# enc28j60.net
KiCad netlist of a schematic drawn in Altium Designer
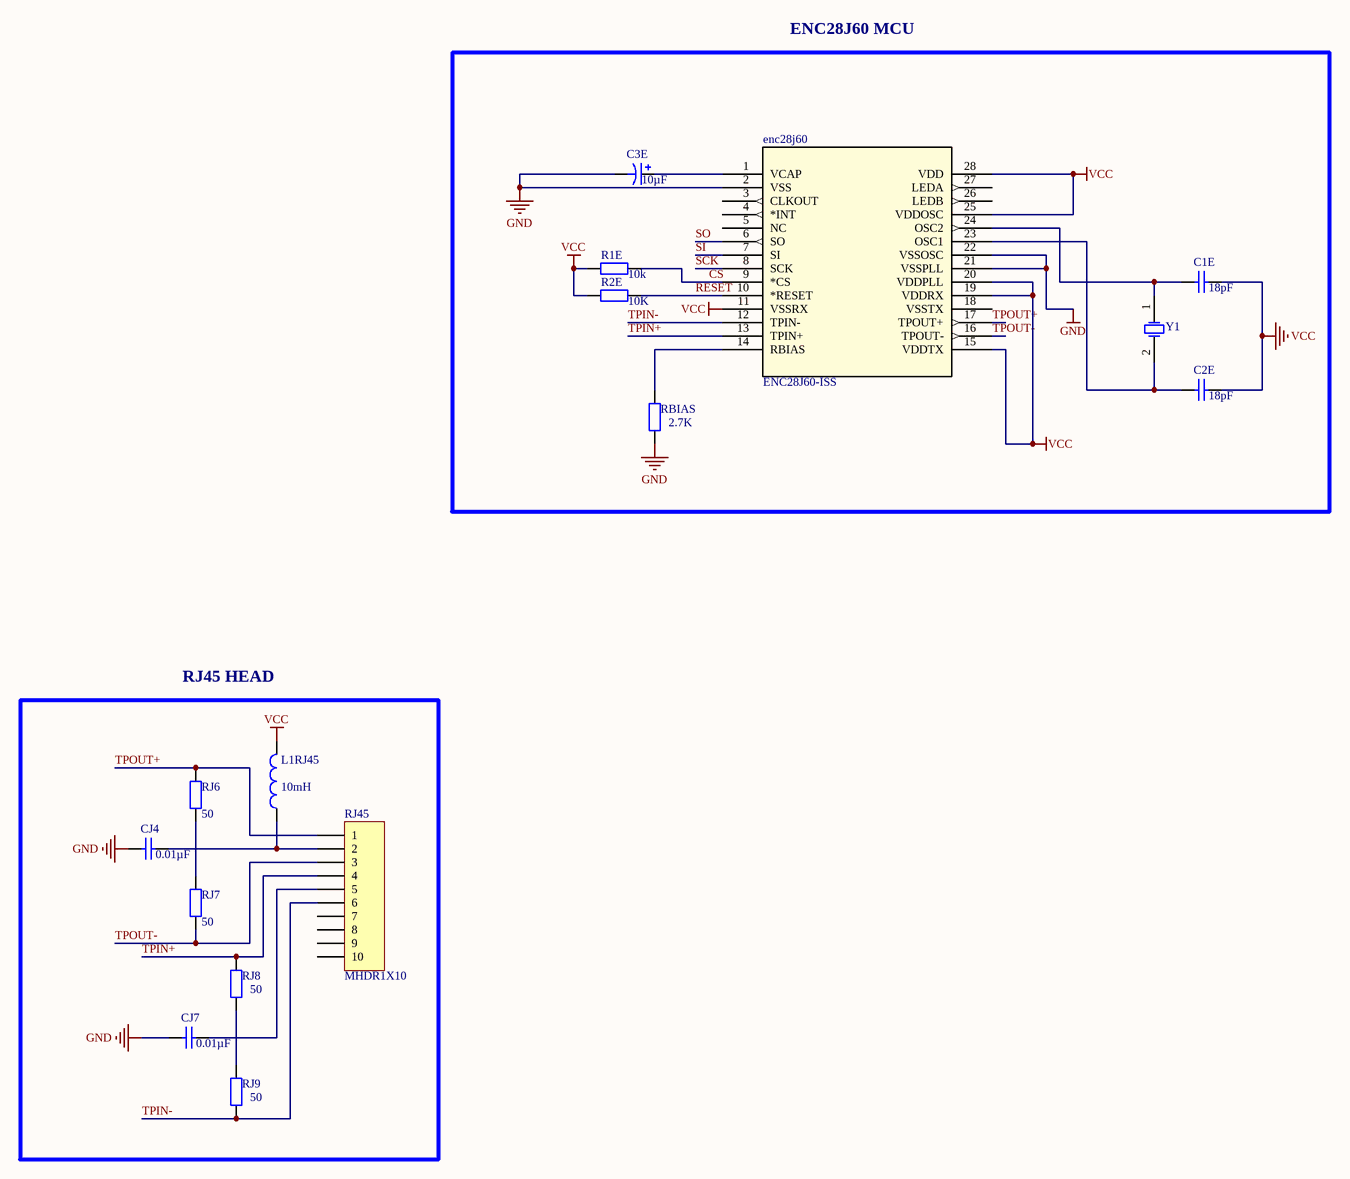
[diagram p0: enc28j60.SchDoc]

(export (version "E")
  (design (tool "Eeschema 10.0.6"))
  (components
    (comp (ref "C1E")
      (value "18pF")
      (footprint "RAD-0.3")
      (description "Capacitor")
      (fields (field (name "Comment") "Cap") (field (name "PUBLISHER") "Altium Limited"))
      (libsource (lib "Miscellaneous Devices") (part "Cap"))
    )
    (comp (ref "C2E")
      (value "18pF")
      (footprint "RAD-0.3")
      (description "Capacitor")
      (fields (field (name "Comment") "Cap") (field (name "PUBLISHER") "Altium Limited"))
      (libsource (lib "Miscellaneous Devices") (part "Cap"))
    )
    (comp (ref "C3E")
      (value "10µF")
      (footprint "RB7.6-15")
      (description "Polarized Capacitor (Radial)")
      (fields (field (name "PUBLISHER") "Altium Limited"))
      (libsource (lib "Miscellaneous Devices") (part "Cap Pol1"))
    )
    (comp (ref "CJ4")
      (value "0.01µF")
      (footprint "RAD-0.3")
      (description "Capacitor")
      (fields (field (name "Comment") "Cap") (field (name "PUBLISHER") "Altium Limited"))
      (libsource (lib "Miscellaneous Devices") (part "Cap"))
    )
    (comp (ref "CJ7")
      (value "0.01µF")
      (footprint "RAD-0.3")
      (description "Capacitor")
      (fields (field (name "Comment") "Cap") (field (name "PUBLISHER") "Altium Limited"))
      (libsource (lib "Miscellaneous Devices") (part "Cap"))
    )
    (comp (ref "enc28j60")
      (value "ENC28J60-ISS")
      (footprint "SSOP28_MC_MCH")
      (description "No Description Available")
      (libsource (lib "ENC28J60-ISS") (part "ENC28J60-ISS"))
    )
    (comp (ref "L1RJ45")
      (value "10mH")
      (footprint "0402-A")
      (description "Inductor")
      (fields (field (name "PUBLISHER") "Altium Limited"))
      (libsource (lib "Miscellaneous Devices") (part "Inductor"))
    )
    (comp (ref "R1E")
      (value "10k")
      (footprint "AXIAL-0.4")
      (description "Resistor")
      (fields (field (name "PUBLISHER") "Altium Limited"))
      (libsource (lib "Miscellaneous Devices") (part "Res2"))
    )
    (comp (ref "R2E")
      (value "10K")
      (footprint "AXIAL-0.4")
      (description "Resistor")
      (fields (field (name "PUBLISHER") "Altium Limited"))
      (libsource (lib "Miscellaneous Devices") (part "Res2"))
    )
    (comp (ref "RBIAS")
      (value "2.7K")
      (footprint "AXIAL-0.4")
      (description "Resistor")
      (fields (field (name "PUBLISHER") "Altium Limited"))
      (libsource (lib "") (part "Res2_1"))
    )
    (comp (ref "RJ6")
      (value "50")
      (footprint "AXIAL-0.4")
      (description "Resistor")
      (fields (field (name "PUBLISHER") "Altium Limited"))
      (libsource (lib "") (part "Res2_1"))
    )
    (comp (ref "RJ7")
      (value "50")
      (footprint "AXIAL-0.4")
      (description "Resistor")
      (fields (field (name "PUBLISHER") "Altium Limited"))
      (libsource (lib "") (part "Res2_1"))
    )
    (comp (ref "RJ8")
      (value "50")
      (footprint "AXIAL-0.4")
      (description "Resistor")
      (fields (field (name "PUBLISHER") "Altium Limited"))
      (libsource (lib "") (part "Res2_1"))
    )
    (comp (ref "RJ9")
      (value "50")
      (footprint "AXIAL-0.4")
      (description "Resistor")
      (fields (field (name "PUBLISHER") "Altium Limited"))
      (libsource (lib "") (part "Res2_1"))
    )
    (comp (ref "RJ45")
      (value "MHDR1X10")
      (footprint "MHDR1X10")
      (description "Header, 10-Pin")
      (fields (field (name "PUBLISHER") "Altium Limited"))
      (libsource (lib "Miscellaneous Connectors") (part "MHDR1X10"))
    )
    (comp (ref "Y1")
      (value "XTAL")
      (footprint "R38")
      (description "Crystal Oscillator")
      (fields (field (name "PUBLISHER") "Altium Limited"))
      (libsource (lib "Miscellaneous Devices") (part "XTAL"))
    )
  )
  (nets
    (net (code "1") (name "/CS") (class "Default")
      (node (ref "R1E") (pin "2") (pinfunction "2_2") (pintype "passive"))
      (node (ref "enc28j60") (pin "9") (pinfunction "*CS_9") (pintype "passive"))
    )
    (net (code "2") (name "/RESET") (class "Default")
      (node (ref "R2E") (pin "2") (pinfunction "2_2") (pintype "passive"))
      (node (ref "enc28j60") (pin "10") (pinfunction "*RESET_10") (pintype "passive"))
    )
    (net (code "3") (name "/SCK") (class "Default")
      (node (ref "enc28j60") (pin "8") (pinfunction "SCK_8") (pintype "passive"))
    )
    (net (code "4") (name "/SI") (class "Default")
      (node (ref "enc28j60") (pin "7") (pinfunction "SI_7") (pintype "passive"))
    )
    (net (code "5") (name "/SO") (class "Default")
      (node (ref "enc28j60") (pin "6") (pinfunction "SO_6") (pintype "output"))
    )
    (net (code "6") (name "/TPIN+") (class "Default")
      (node (ref "RJ45") (pin "4") (pinfunction "4_4") (pintype "passive"))
      (node (ref "RJ8") (pin "2") (pinfunction "2_2") (pintype "passive"))
      (node (ref "enc28j60") (pin "13") (pinfunction "TPIN+_13") (pintype "passive"))
    )
    (net (code "7") (name "/TPIN-") (class "Default")
      (node (ref "RJ45") (pin "6") (pinfunction "6_6") (pintype "passive"))
      (node (ref "RJ9") (pin "1") (pinfunction "1_1") (pintype "passive"))
      (node (ref "enc28j60") (pin "12") (pinfunction "TPIN-_12") (pintype "passive"))
    )
    (net (code "8") (name "/TPOUT+") (class "Default")
      (node (ref "RJ45") (pin "1") (pinfunction "1_1") (pintype "passive"))
      (node (ref "RJ6") (pin "2") (pinfunction "2_2") (pintype "passive"))
      (node (ref "enc28j60") (pin "17") (pinfunction "TPOUT+_17") (pintype "output"))
    )
    (net (code "9") (name "/TPOUT-") (class "Default")
      (node (ref "RJ45") (pin "3") (pinfunction "3_3") (pintype "passive"))
      (node (ref "RJ7") (pin "1") (pinfunction "1_1") (pintype "passive"))
      (node (ref "enc28j60") (pin "16") (pinfunction "TPOUT-_16") (pintype "output"))
    )
    (net (code "10") (name "GND") (class "Default")
      (node (ref "C3E") (pin "2") (pinfunction "2_2") (pintype "passive"))
      (node (ref "CJ4") (pin "1") (pinfunction "1_1") (pintype "passive"))
      (node (ref "CJ7") (pin "1") (pinfunction "1_1") (pintype "passive"))
      (node (ref "RBIAS") (pin "1") (pinfunction "1_1") (pintype "passive"))
      (node (ref "enc28j60") (pin "2") (pinfunction "VSS_2") (pintype "power_in"))
      (node (ref "enc28j60") (pin "21") (pinfunction "VSSPLL_21") (pintype "power_in"))
      (node (ref "enc28j60") (pin "22") (pinfunction "VSSOSC_22") (pintype "power_in"))
    )
    (net (code "11") (name "Net-(CJ4-Pad2)") (class "Default")
      (node (ref "CJ4") (pin "2") (pinfunction "2_2") (pintype "passive"))
      (node (ref "L1RJ45") (pin "1") (pinfunction "1_1") (pintype "passive"))
      (node (ref "RJ45") (pin "2") (pinfunction "2_2") (pintype "passive"))
    )
    (net (code "12") (name "Net-(CJ7-Pad2)") (class "Default")
      (node (ref "CJ7") (pin "2") (pinfunction "2_2") (pintype "passive"))
      (node (ref "RJ45") (pin "5") (pinfunction "5_5") (pintype "passive"))
    )
    (net (code "13") (name "Net-(RJ6-Pad1)") (class "Default")
      (node (ref "RJ6") (pin "1") (pinfunction "1_1") (pintype "passive"))
      (node (ref "RJ7") (pin "2") (pinfunction "2_2") (pintype "passive"))
    )
    (net (code "14") (name "Net-(RJ8-Pad1)") (class "Default")
      (node (ref "RJ8") (pin "1") (pinfunction "1_1") (pintype "passive"))
      (node (ref "RJ9") (pin "2") (pinfunction "2_2") (pintype "passive"))
    )
    (net (code "15") (name "Net-(Y1-OSC1)") (class "Default")
      (node (ref "C1E") (pin "1") (pinfunction "1_1") (pintype "passive"))
      (node (ref "Y1") (pin "1") (pinfunction "OSC1_1") (pintype "passive"))
      (node (ref "enc28j60") (pin "24") (pinfunction "OSC2_24") (pintype "output"))
    )
    (net (code "16") (name "Net-(Y1-OSC2)") (class "Default")
      (node (ref "C2E") (pin "1") (pinfunction "1_1") (pintype "passive"))
      (node (ref "Y1") (pin "2") (pinfunction "OSC2_2") (pintype "passive"))
      (node (ref "enc28j60") (pin "23") (pinfunction "OSC1_23") (pintype "passive"))
    )
    (net (code "17") (name "Net-(enc28j60-RBIAS)") (class "Default")
      (node (ref "RBIAS") (pin "2") (pinfunction "2_2") (pintype "passive"))
      (node (ref "enc28j60") (pin "14") (pinfunction "RBIAS_14") (pintype "passive"))
    )
    (net (code "18") (name "Net-(enc28j60-VCAP)") (class "Default")
      (node (ref "C3E") (pin "1") (pinfunction "1_1") (pintype "passive"))
      (node (ref "enc28j60") (pin "1") (pinfunction "VCAP_1") (pintype "power_in"))
    )
    (net (code "19") (name "VCC") (class "Default")
      (node (ref "C1E") (pin "2") (pinfunction "2_2") (pintype "passive"))
      (node (ref "C2E") (pin "2") (pinfunction "2_2") (pintype "passive"))
      (node (ref "L1RJ45") (pin "2") (pinfunction "2_2") (pintype "passive"))
      (node (ref "R1E") (pin "1") (pinfunction "1_1") (pintype "passive"))
      (node (ref "R2E") (pin "1") (pinfunction "1_1") (pintype "passive"))
      (node (ref "enc28j60") (pin "11") (pinfunction "VSSRX_11") (pintype "power_in"))
      (node (ref "enc28j60") (pin "15") (pinfunction "VDDTX_15") (pintype "power_in"))
      (node (ref "enc28j60") (pin "19") (pinfunction "VDDRX_19") (pintype "power_in"))
      (node (ref "enc28j60") (pin "20") (pinfunction "VDDPLL_20") (pintype "power_in"))
      (node (ref "enc28j60") (pin "25") (pinfunction "VDDOSC_25") (pintype "power_in"))
      (node (ref "enc28j60") (pin "28") (pinfunction "VDD_28") (pintype "power_in"))
    )
    (net (code "20") (name "unconnected-(RJ45-Pad7)") (class "Default")
      (node (ref "RJ45") (pin "7") (pinfunction "7_7") (pintype "passive"))
    )
    (net (code "21") (name "unconnected-(RJ45-Pad8)") (class "Default")
      (node (ref "RJ45") (pin "8") (pinfunction "8_8") (pintype "passive"))
    )
    (net (code "22") (name "unconnected-(RJ45-Pad9)") (class "Default")
      (node (ref "RJ45") (pin "9") (pinfunction "9_9") (pintype "passive"))
    )
    (net (code "23") (name "unconnected-(RJ45-Pad10)") (class "Default")
      (node (ref "RJ45") (pin "10") (pinfunction "10_10") (pintype "passive"))
    )
    (net (code "24") (name "unconnected-(enc28j60-*INT-Pad4)") (class "Default")
      (node (ref "enc28j60") (pin "4") (pinfunction "*INT_4") (pintype "output"))
    )
    (net (code "25") (name "unconnected-(enc28j60-CLKOUT-Pad3)") (class "Default")
      (node (ref "enc28j60") (pin "3") (pinfunction "CLKOUT_3") (pintype "output"))
    )
    (net (code "26") (name "unconnected-(enc28j60-LEDA-Pad27)") (class "Default")
      (node (ref "enc28j60") (pin "27") (pinfunction "LEDA_27") (pintype "output"))
    )
    (net (code "27") (name "unconnected-(enc28j60-LEDB-Pad26)") (class "Default")
      (node (ref "enc28j60") (pin "26") (pinfunction "LEDB_26") (pintype "output"))
    )
    (net (code "28") (name "unconnected-(enc28j60-NC-Pad5)") (class "Default")
      (node (ref "enc28j60") (pin "5") (pinfunction "NC_5") (pintype "passive"))
    )
    (net (code "29") (name "unconnected-(enc28j60-VSSTX-Pad18)") (class "Default")
      (node (ref "enc28j60") (pin "18") (pinfunction "VSSTX_18") (pintype "power_in"))
    )
  )
)
